# SNAC_7ch_USB3-5v.net
KiCad netlist of a schematic drawn in EAGLE
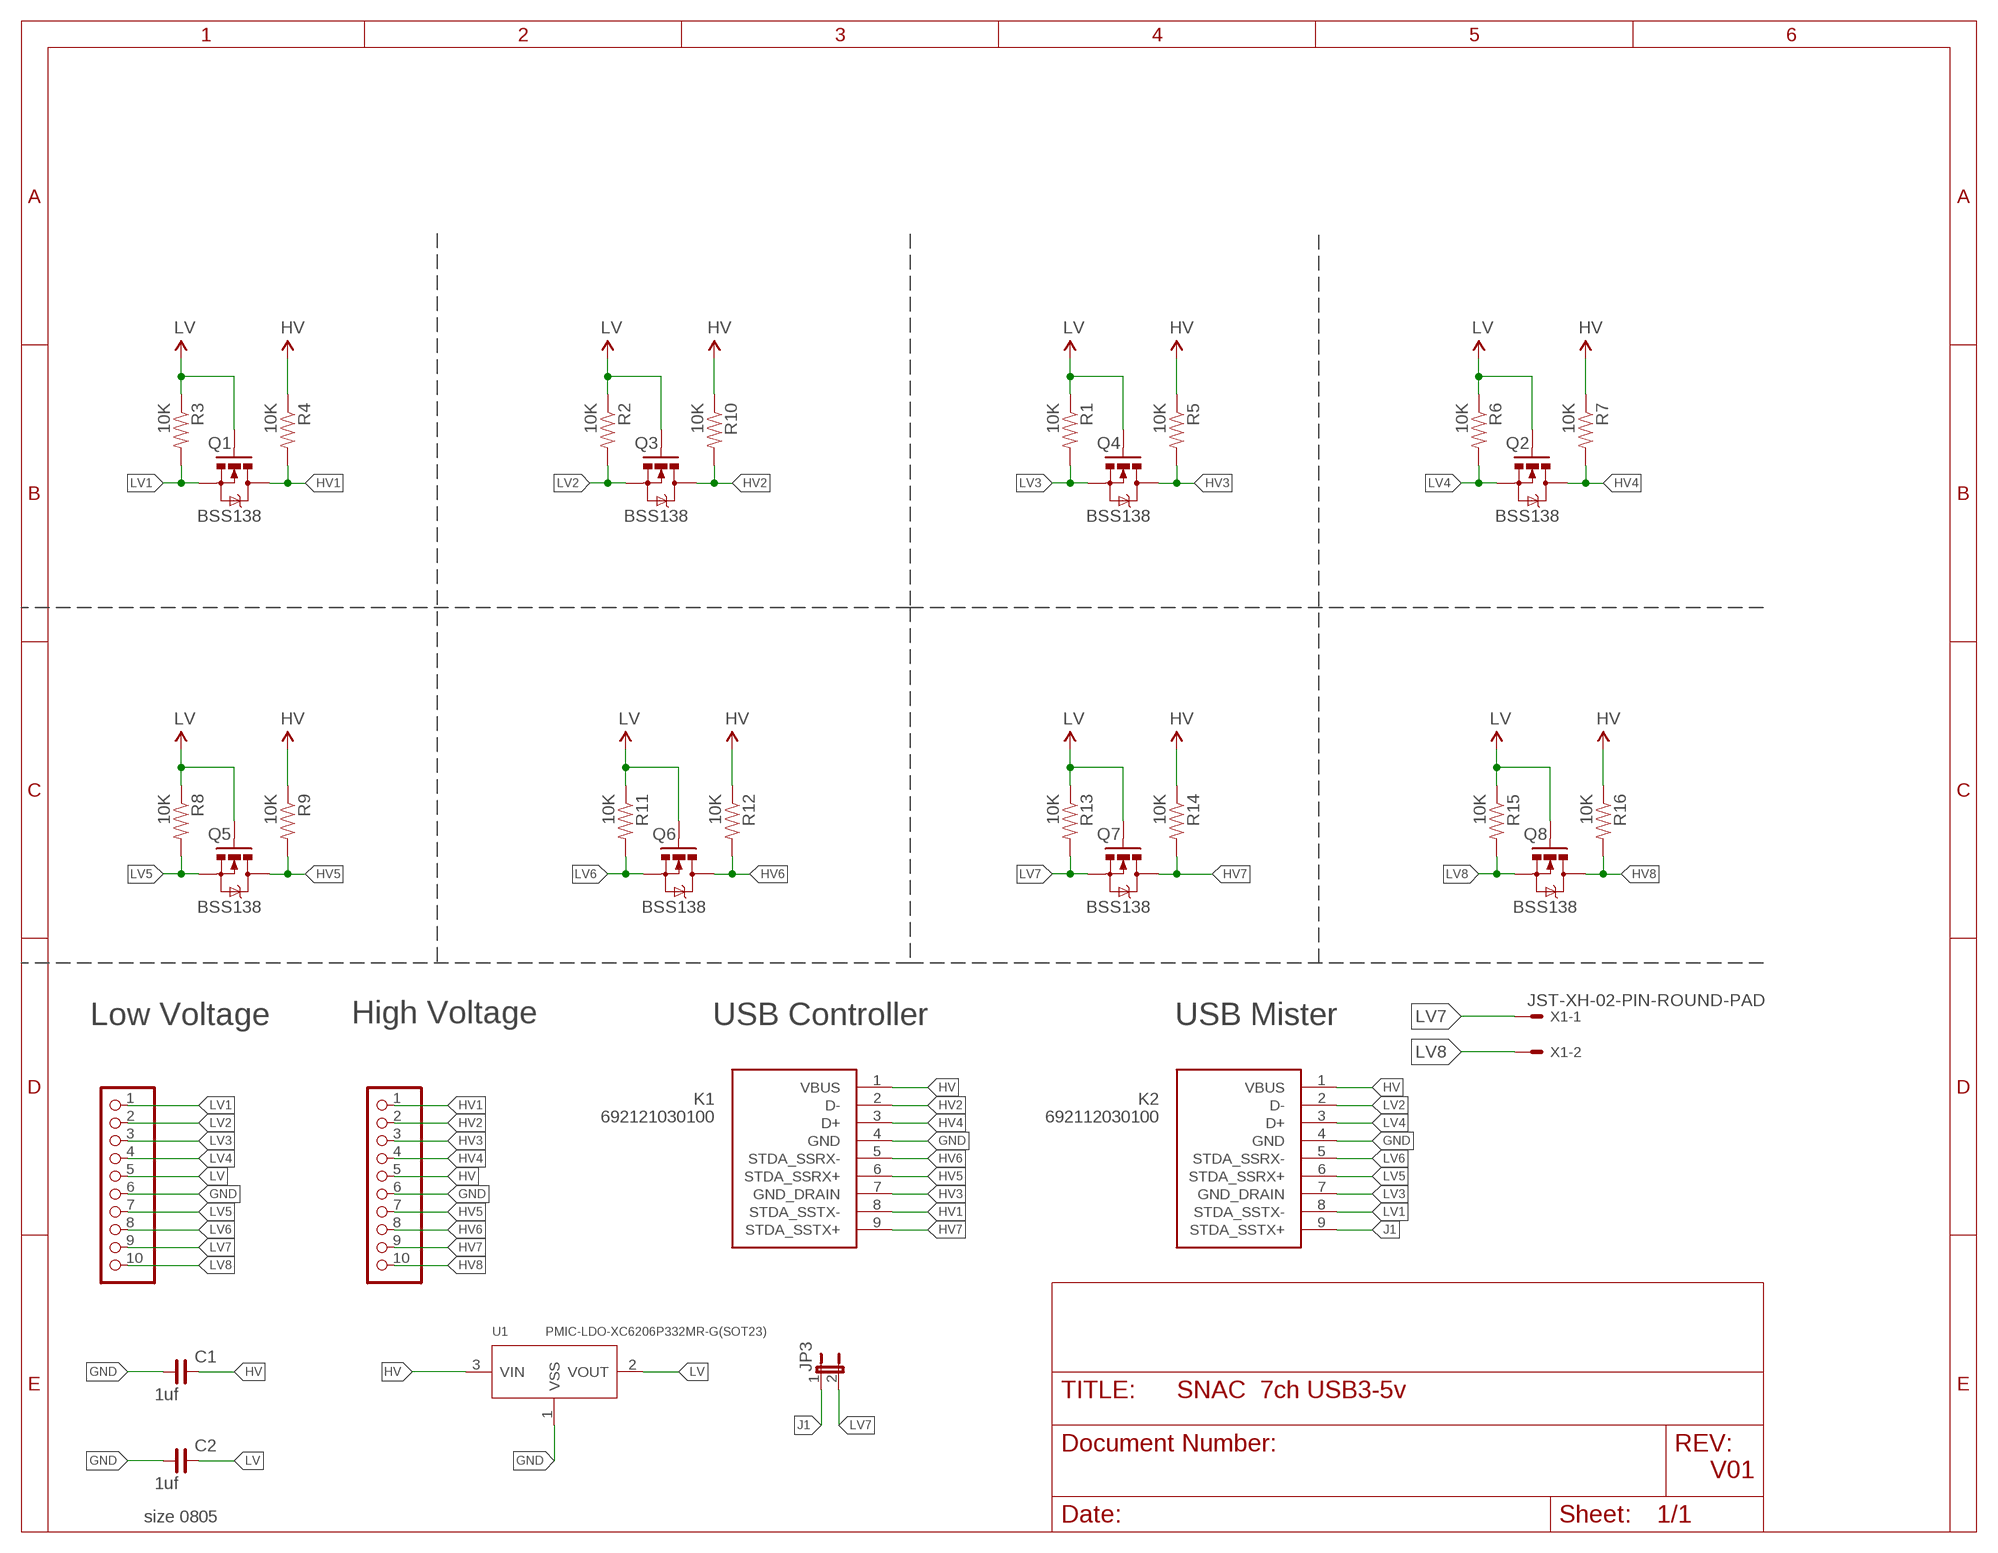
[diagram p0: schematic, sheet 1]

(export (version "E")
  (design (tool "Eeschema 10.0.6"))
  (components
    (comp (ref "C1")
      (value "1uf")
      (footprint "eagle-import:C0805")
      (libsource (lib "eagle-import") (part "C_0805"))
    )
    (comp (ref "C2")
      (value "1uf")
      (footprint "eagle-import:C0805")
      (libsource (lib "eagle-import") (part "C_0805"))
    )
    (comp (ref "JP1")
      (value "PINHD-1X10_2.54-S")
      (footprint "eagle-import:1X10-S")
      (libsource (lib "eagle-import") (part "PINHD-1X10_2.54-S"))
    )
    (comp (ref "JP2")
      (value "PINHD-1X10_2.54-S")
      (footprint "eagle-import:1X10-S")
      (libsource (lib "eagle-import") (part "PINHD-1X10_2.54-S"))
    )
    (comp (ref "JP3")
      (value "JUMPER-2PTH")
      (footprint "eagle-import:1X02")
      (libsource (lib "eagle-import") (part "JUMPER-2PTH"))
    )
    (comp (ref "K1")
      (value "692121030100")
      (footprint "eagle-import:692121030100")
      (libsource (lib "eagle-import") (part "692121030100"))
    )
    (comp (ref "K2")
      (value "692112030100")
      (footprint "eagle-import:692112030100")
      (libsource (lib "eagle-import") (part "692112030100"))
    )
    (comp (ref "Q1")
      (value "BSS138")
      (footprint "eagle-import:SOT23-3")
      (libsource (lib "eagle-import") (part "MOSFET-NCHANNELSMD"))
    )
    (comp (ref "Q2")
      (value "BSS138")
      (footprint "eagle-import:SOT23-3")
      (libsource (lib "eagle-import") (part "MOSFET-NCHANNELSMD"))
    )
    (comp (ref "Q3")
      (value "BSS138")
      (footprint "eagle-import:SOT23-3")
      (libsource (lib "eagle-import") (part "MOSFET-NCHANNELSMD"))
    )
    (comp (ref "Q4")
      (value "BSS138")
      (footprint "eagle-import:SOT23-3")
      (libsource (lib "eagle-import") (part "MOSFET-NCHANNELSMD"))
    )
    (comp (ref "Q5")
      (value "BSS138")
      (footprint "eagle-import:SOT23-3")
      (libsource (lib "eagle-import") (part "MOSFET-NCHANNELSMD"))
    )
    (comp (ref "Q6")
      (value "BSS138")
      (footprint "eagle-import:SOT23-3")
      (libsource (lib "eagle-import") (part "MOSFET-NCHANNELSMD"))
    )
    (comp (ref "Q7")
      (value "BSS138")
      (footprint "eagle-import:SOT23-3")
      (libsource (lib "eagle-import") (part "MOSFET-NCHANNELSMD"))
    )
    (comp (ref "Q8")
      (value "BSS138")
      (footprint "eagle-import:SOT23-3")
      (libsource (lib "eagle-import") (part "MOSFET-NCHANNELSMD"))
    )
    (comp (ref "R1")
      (value "10K")
      (footprint "eagle-import:0603-RES")
      (libsource (lib "eagle-import") (part "RESISTOR0603-RES"))
    )
    (comp (ref "R2")
      (value "10K")
      (footprint "eagle-import:0603-RES")
      (libsource (lib "eagle-import") (part "RESISTOR0603-RES"))
    )
    (comp (ref "R3")
      (value "10K")
      (footprint "eagle-import:0603-RES")
      (libsource (lib "eagle-import") (part "RESISTOR0603-RES"))
    )
    (comp (ref "R4")
      (value "10K")
      (footprint "eagle-import:0603-RES")
      (libsource (lib "eagle-import") (part "RESISTOR0603-RES"))
    )
    (comp (ref "R5")
      (value "10K")
      (footprint "eagle-import:0603-RES")
      (libsource (lib "eagle-import") (part "RESISTOR0603-RES"))
    )
    (comp (ref "R6")
      (value "10K")
      (footprint "eagle-import:0603-RES")
      (libsource (lib "eagle-import") (part "RESISTOR0603-RES"))
    )
    (comp (ref "R7")
      (value "10K")
      (footprint "eagle-import:0603-RES")
      (libsource (lib "eagle-import") (part "RESISTOR0603-RES"))
    )
    (comp (ref "R8")
      (value "10K")
      (footprint "eagle-import:0603-RES")
      (libsource (lib "eagle-import") (part "RESISTOR0603-RES"))
    )
    (comp (ref "R9")
      (value "10K")
      (footprint "eagle-import:0603-RES")
      (libsource (lib "eagle-import") (part "RESISTOR0603-RES"))
    )
    (comp (ref "R10")
      (value "10K")
      (footprint "eagle-import:0603-RES")
      (libsource (lib "eagle-import") (part "RESISTOR0603-RES"))
    )
    (comp (ref "R11")
      (value "10K")
      (footprint "eagle-import:0603-RES")
      (libsource (lib "eagle-import") (part "RESISTOR0603-RES"))
    )
    (comp (ref "R12")
      (value "10K")
      (footprint "eagle-import:0603-RES")
      (libsource (lib "eagle-import") (part "RESISTOR0603-RES"))
    )
    (comp (ref "R13")
      (value "10K")
      (footprint "eagle-import:0603-RES")
      (libsource (lib "eagle-import") (part "RESISTOR0603-RES"))
    )
    (comp (ref "R14")
      (value "10K")
      (footprint "eagle-import:0603-RES")
      (libsource (lib "eagle-import") (part "RESISTOR0603-RES"))
    )
    (comp (ref "R15")
      (value "10K")
      (footprint "eagle-import:0603-RES")
      (libsource (lib "eagle-import") (part "RESISTOR0603-RES"))
    )
    (comp (ref "R16")
      (value "10K")
      (footprint "eagle-import:0603-RES")
      (libsource (lib "eagle-import") (part "RESISTOR0603-RES"))
    )
    (comp (ref "U1")
      (value "PMIC-LDO-XC6206P332MR-G(SOT23)")
      (footprint "eagle-import:SOT-23")
      (fields (field (name "MF") "Torex") (field (name "MP") "XC6206P332MR-G"))
      (libsource (lib "eagle-import") (part "PMIC-LDO-XC6206P332MR-G(SOT23)"))
    )
    (comp (ref "X1")
      (value "JST-XH-02-PIN-ROUND-PAD")
      (footprint "eagle-import:JST-XH-02-PACKAGE-ROUND-PAD")
      (libsource (lib "eagle-import") (part "JST-XH-02-PIN-ROUND-PAD"))
    )
  )
  (nets
    (net (code "1") (name "GND") (class "Default")
      (node (ref "C1") (pin "1") (pinfunction "1_1") (pintype "passive"))
      (node (ref "C2") (pin "1") (pinfunction "1_1") (pintype "passive"))
      (node (ref "JP1") (pin "6") (pinfunction "6_6") (pintype "passive"))
      (node (ref "JP2") (pin "6") (pinfunction "6_6") (pintype "passive"))
      (node (ref "K1") (pin "4") (pinfunction "GND_4") (pintype "bidirectional"))
      (node (ref "K2") (pin "4") (pinfunction "GND_4") (pintype "bidirectional"))
      (node (ref "U1") (pin "1") (pinfunction "VSS_1") (pintype "power_in"))
    )
    (net (code "2") (name "HV") (class "Default")
      (node (ref "C1") (pin "2") (pinfunction "2_2") (pintype "passive"))
      (node (ref "JP2") (pin "5") (pinfunction "5_5") (pintype "passive"))
      (node (ref "K1") (pin "1") (pinfunction "VBUS_1") (pintype "bidirectional"))
      (node (ref "K2") (pin "1") (pinfunction "VBUS_1") (pintype "bidirectional"))
      (node (ref "R10") (pin "1") (pinfunction "1_1") (pintype "passive"))
      (node (ref "R12") (pin "1") (pinfunction "1_1") (pintype "passive"))
      (node (ref "R14") (pin "1") (pinfunction "1_1") (pintype "passive"))
      (node (ref "R16") (pin "1") (pinfunction "1_1") (pintype "passive"))
      (node (ref "R4") (pin "1") (pinfunction "1_1") (pintype "passive"))
      (node (ref "R5") (pin "1") (pinfunction "1_1") (pintype "passive"))
      (node (ref "R7") (pin "1") (pinfunction "1_1") (pintype "passive"))
      (node (ref "R9") (pin "1") (pinfunction "1_1") (pintype "passive"))
      (node (ref "U1") (pin "3") (pinfunction "VIN_3") (pintype "input"))
    )
    (net (code "3") (name "HV1") (class "Default")
      (node (ref "JP2") (pin "1") (pinfunction "1_1") (pintype "passive"))
      (node (ref "K1") (pin "8") (pinfunction "STDA_SSTX-_8") (pintype "bidirectional"))
      (node (ref "Q1") (pin "3") (pinfunction "D_3") (pintype "passive"))
      (node (ref "R4") (pin "2") (pinfunction "2_2") (pintype "passive"))
    )
    (net (code "4") (name "HV2") (class "Default")
      (node (ref "JP2") (pin "2") (pinfunction "2_2") (pintype "passive"))
      (node (ref "K1") (pin "2") (pinfunction "D-_2") (pintype "bidirectional"))
      (node (ref "Q3") (pin "3") (pinfunction "D_3") (pintype "passive"))
      (node (ref "R10") (pin "2") (pinfunction "2_2") (pintype "passive"))
    )
    (net (code "5") (name "HV3") (class "Default")
      (node (ref "JP2") (pin "3") (pinfunction "3_3") (pintype "passive"))
      (node (ref "K1") (pin "7") (pinfunction "GND_DRAIN_7") (pintype "bidirectional"))
      (node (ref "Q4") (pin "3") (pinfunction "D_3") (pintype "passive"))
      (node (ref "R5") (pin "2") (pinfunction "2_2") (pintype "passive"))
    )
    (net (code "6") (name "HV4") (class "Default")
      (node (ref "JP2") (pin "4") (pinfunction "4_4") (pintype "passive"))
      (node (ref "K1") (pin "3") (pinfunction "D+_3") (pintype "bidirectional"))
      (node (ref "Q2") (pin "3") (pinfunction "D_3") (pintype "passive"))
      (node (ref "R7") (pin "2") (pinfunction "2_2") (pintype "passive"))
    )
    (net (code "7") (name "HV5") (class "Default")
      (node (ref "JP2") (pin "7") (pinfunction "7_7") (pintype "passive"))
      (node (ref "K1") (pin "6") (pinfunction "STDA_SSRX+_6") (pintype "bidirectional"))
      (node (ref "Q5") (pin "3") (pinfunction "D_3") (pintype "passive"))
      (node (ref "R9") (pin "2") (pinfunction "2_2") (pintype "passive"))
    )
    (net (code "8") (name "HV6") (class "Default")
      (node (ref "JP2") (pin "8") (pinfunction "8_8") (pintype "passive"))
      (node (ref "K1") (pin "5") (pinfunction "STDA_SSRX-_5") (pintype "bidirectional"))
      (node (ref "Q6") (pin "3") (pinfunction "D_3") (pintype "passive"))
      (node (ref "R12") (pin "2") (pinfunction "2_2") (pintype "passive"))
    )
    (net (code "9") (name "HV7") (class "Default")
      (node (ref "JP2") (pin "9") (pinfunction "9_9") (pintype "passive"))
      (node (ref "K1") (pin "9") (pinfunction "STDA_SSTX+_9") (pintype "bidirectional"))
      (node (ref "Q7") (pin "3") (pinfunction "D_3") (pintype "passive"))
      (node (ref "R14") (pin "2") (pinfunction "2_2") (pintype "passive"))
    )
    (net (code "10") (name "HV8") (class "Default")
      (node (ref "JP2") (pin "10") (pinfunction "10_10") (pintype "passive"))
      (node (ref "Q8") (pin "3") (pinfunction "D_3") (pintype "passive"))
      (node (ref "R16") (pin "2") (pinfunction "2_2") (pintype "passive"))
    )
    (net (code "11") (name "J1") (class "Default")
      (node (ref "JP3") (pin "1") (pinfunction "1_1") (pintype "passive"))
      (node (ref "K2") (pin "9") (pinfunction "STDA_SSTX+_9") (pintype "bidirectional"))
    )
    (net (code "12") (name "LV") (class "Default")
      (node (ref "C2") (pin "2") (pinfunction "2_2") (pintype "passive"))
      (node (ref "JP1") (pin "5") (pinfunction "5_5") (pintype "passive"))
      (node (ref "Q1") (pin "1") (pinfunction "G_1") (pintype "passive"))
      (node (ref "Q2") (pin "1") (pinfunction "G_1") (pintype "passive"))
      (node (ref "Q3") (pin "1") (pinfunction "G_1") (pintype "passive"))
      (node (ref "Q4") (pin "1") (pinfunction "G_1") (pintype "passive"))
      (node (ref "Q5") (pin "1") (pinfunction "G_1") (pintype "passive"))
      (node (ref "Q6") (pin "1") (pinfunction "G_1") (pintype "passive"))
      (node (ref "Q7") (pin "1") (pinfunction "G_1") (pintype "passive"))
      (node (ref "Q8") (pin "1") (pinfunction "G_1") (pintype "passive"))
      (node (ref "R1") (pin "1") (pinfunction "1_1") (pintype "passive"))
      (node (ref "R11") (pin "1") (pinfunction "1_1") (pintype "passive"))
      (node (ref "R13") (pin "1") (pinfunction "1_1") (pintype "passive"))
      (node (ref "R15") (pin "1") (pinfunction "1_1") (pintype "passive"))
      (node (ref "R2") (pin "1") (pinfunction "1_1") (pintype "passive"))
      (node (ref "R3") (pin "1") (pinfunction "1_1") (pintype "passive"))
      (node (ref "R6") (pin "1") (pinfunction "1_1") (pintype "passive"))
      (node (ref "R8") (pin "1") (pinfunction "1_1") (pintype "passive"))
      (node (ref "U1") (pin "2") (pinfunction "VOUT_2") (pintype "output"))
    )
    (net (code "13") (name "LV1") (class "Default")
      (node (ref "JP1") (pin "1") (pinfunction "1_1") (pintype "passive"))
      (node (ref "K2") (pin "8") (pinfunction "STDA_SSTX-_8") (pintype "bidirectional"))
      (node (ref "Q1") (pin "2") (pinfunction "S_2") (pintype "passive"))
      (node (ref "R3") (pin "2") (pinfunction "2_2") (pintype "passive"))
    )
    (net (code "14") (name "LV2") (class "Default")
      (node (ref "JP1") (pin "2") (pinfunction "2_2") (pintype "passive"))
      (node (ref "K2") (pin "2") (pinfunction "D-_2") (pintype "bidirectional"))
      (node (ref "Q3") (pin "2") (pinfunction "S_2") (pintype "passive"))
      (node (ref "R2") (pin "2") (pinfunction "2_2") (pintype "passive"))
    )
    (net (code "15") (name "LV3") (class "Default")
      (node (ref "JP1") (pin "3") (pinfunction "3_3") (pintype "passive"))
      (node (ref "K2") (pin "7") (pinfunction "GND_DRAIN_7") (pintype "bidirectional"))
      (node (ref "Q4") (pin "2") (pinfunction "S_2") (pintype "passive"))
      (node (ref "R1") (pin "2") (pinfunction "2_2") (pintype "passive"))
    )
    (net (code "16") (name "LV4") (class "Default")
      (node (ref "JP1") (pin "4") (pinfunction "4_4") (pintype "passive"))
      (node (ref "K2") (pin "3") (pinfunction "D+_3") (pintype "bidirectional"))
      (node (ref "Q2") (pin "2") (pinfunction "S_2") (pintype "passive"))
      (node (ref "R6") (pin "2") (pinfunction "2_2") (pintype "passive"))
    )
    (net (code "17") (name "LV5") (class "Default")
      (node (ref "JP1") (pin "7") (pinfunction "7_7") (pintype "passive"))
      (node (ref "K2") (pin "6") (pinfunction "STDA_SSRX+_6") (pintype "bidirectional"))
      (node (ref "Q5") (pin "2") (pinfunction "S_2") (pintype "passive"))
      (node (ref "R8") (pin "2") (pinfunction "2_2") (pintype "passive"))
    )
    (net (code "18") (name "LV6") (class "Default")
      (node (ref "JP1") (pin "8") (pinfunction "8_8") (pintype "passive"))
      (node (ref "K2") (pin "5") (pinfunction "STDA_SSRX-_5") (pintype "bidirectional"))
      (node (ref "Q6") (pin "2") (pinfunction "S_2") (pintype "passive"))
      (node (ref "R11") (pin "2") (pinfunction "2_2") (pintype "passive"))
    )
    (net (code "19") (name "LV7") (class "Default")
      (node (ref "JP1") (pin "9") (pinfunction "9_9") (pintype "passive"))
      (node (ref "JP3") (pin "2") (pinfunction "2_2") (pintype "passive"))
      (node (ref "Q7") (pin "2") (pinfunction "S_2") (pintype "passive"))
      (node (ref "R13") (pin "2") (pinfunction "2_2") (pintype "passive"))
      (node (ref "X1") (pin "1") (pinfunction "S_1") (pintype "passive"))
    )
    (net (code "20") (name "LV8") (class "Default")
      (node (ref "JP1") (pin "10") (pinfunction "10_10") (pintype "passive"))
      (node (ref "Q8") (pin "2") (pinfunction "S_2") (pintype "passive"))
      (node (ref "R15") (pin "2") (pinfunction "2_2") (pintype "passive"))
      (node (ref "X1") (pin "2") (pinfunction "S_2") (pintype "passive"))
    )
  )
)
